# processor_beaglebone.net
KiCad netlist of a schematic drawn in Altium Designer
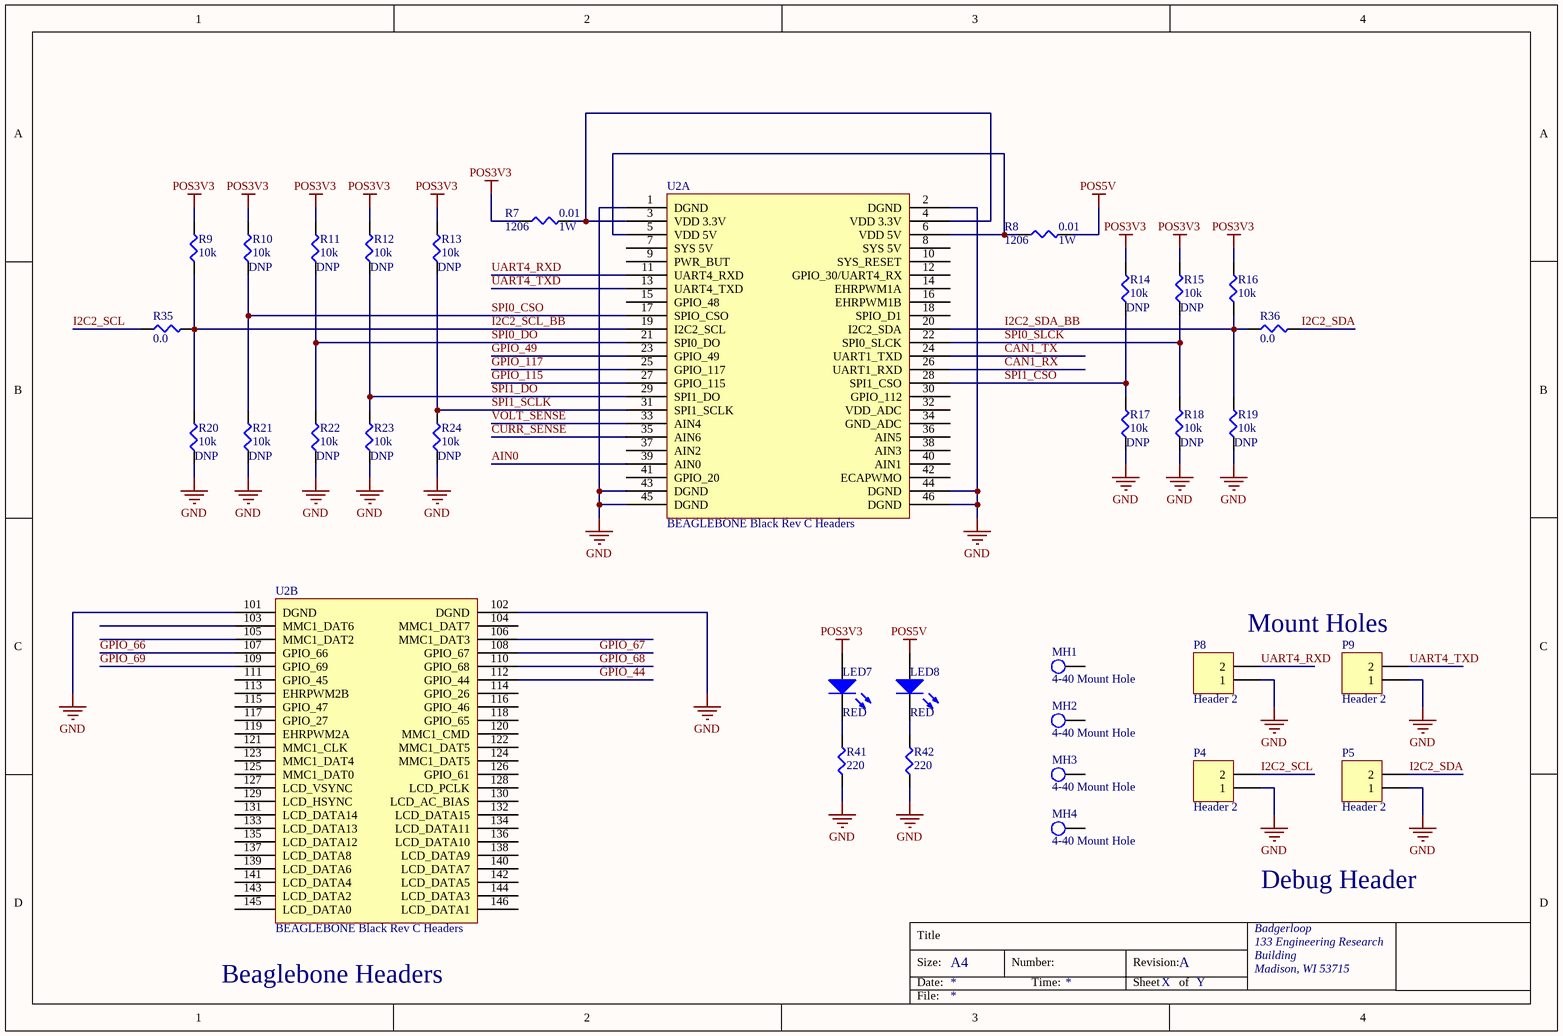
[diagram p0: processor_beaglebone.SchDoc]

(export (version "E")
  (design (tool "Eeschema 10.0.6"))
  (components
    (comp (ref "LED7")
      (value "RED")
      (footprint "LED 0603 RED")
      (description "Red 631nm LED Indication - Discrete 2V 0603 (1608 Metric)")
      (fields (field (name "MANUFACTURER") "Lite-On Inc."))
      (libsource (lib "misc") (part "LED RED 0603"))
    )
    (comp (ref "LED8")
      (value "RED")
      (footprint "LED 0603 RED")
      (description "Red 631nm LED Indication - Discrete 2V 0603 (1608 Metric)")
      (fields (field (name "MANUFACTURER") "Lite-On Inc."))
      (libsource (lib "misc") (part "LED RED 0603"))
    )
    (comp (ref "MH1")
      (value "4-40 Mount Hole")
      (footprint "MH")
      (libsource (lib "misc") (part "4-40 Mount Hole"))
    )
    (comp (ref "MH2")
      (value "4-40 Mount Hole")
      (footprint "MH")
      (libsource (lib "misc") (part "4-40 Mount Hole"))
    )
    (comp (ref "MH3")
      (value "4-40 Mount Hole")
      (footprint "MH")
      (libsource (lib "misc") (part "4-40 Mount Hole"))
    )
    (comp (ref "MH4")
      (value "4-40 Mount Hole")
      (footprint "MH")
      (libsource (lib "misc") (part "4-40 Mount Hole"))
    )
    (comp (ref "P4")
      (value "Header 2")
      (footprint "Pin Header 1x2 TH Pitch 2.54mm")
      (description "Header, 2-Pin")
      (fields (field (name "PUBLISHER") "Altium Limited"))
      (libsource (lib "connector") (part "Header 2"))
    )
    (comp (ref "P5")
      (value "Header 2")
      (footprint "Pin Header 1x2 TH Pitch 2.54mm")
      (description "Header, 2-Pin")
      (fields (field (name "PUBLISHER") "Altium Limited"))
      (libsource (lib "connector") (part "Header 2"))
    )
    (comp (ref "P8")
      (value "Header 2")
      (footprint "Pin Header 1x2 TH Pitch 2.54mm")
      (description "Header, 2-Pin")
      (fields (field (name "PUBLISHER") "Altium Limited"))
      (libsource (lib "connector") (part "Header 2"))
    )
    (comp (ref "P9")
      (value "Header 2")
      (footprint "Pin Header 1x2 TH Pitch 2.54mm")
      (description "Header, 2-Pin")
      (fields (field (name "PUBLISHER") "Altium Limited"))
      (libsource (lib "connector") (part "Header 2"))
    )
    (comp (ref "R7")
      (value "0.01")
      (footprint "SMD-1206-RES")
      (description "RES SMD 0.01 OHM 1% 1W 1206")
      (fields
        (field (name "PART NUMBER") "ERJ-8CWFR010V")
        (field (name "DIGI-KEY PART NUMBER") "P0.01BVCT-ND")
        (field (name "POWER (WATTS)") "1W")
        (field (name "SUPPLIER DEVICE PACKAGE") "1206")
      )
      (libsource (lib "resistor") (part "ERJ-8CWFR010V"))
    )
    (comp (ref "R8")
      (value "0.01")
      (footprint "SMD-1206-RES")
      (description "RES SMD 0.01 OHM 1% 1W 1206")
      (fields
        (field (name "PART NUMBER") "ERJ-8CWFR010V")
        (field (name "DIGI-KEY PART NUMBER") "P0.01BVCT-ND")
        (field (name "POWER (WATTS)") "1W")
        (field (name "SUPPLIER DEVICE PACKAGE") "1206")
      )
      (libsource (lib "resistor") (part "ERJ-8CWFR010V"))
    )
    (comp (ref "R9")
      (value "10k")
      (footprint "SMD-0402-RES")
      (description "RES SMD 10K OHM 5% 1/10W 0402")
      (fields (field (name "PART NUMBER") "ERJ-2GEJ103X") (field (name "DIGI-KEY PART NUMBER") "P10KJCT-ND"))
      (libsource (lib "resistor") (part "ERJ-2GEJ103X"))
    )
    (comp (ref "R10")
      (value "10k")
      (footprint "SMD-0402-RES")
      (description "RES SMD 10K OHM 5% 1/10W 0402")
      (fields
        (field (name "PART NUMBER") "ERJ-2GEJ103X")
        (field (name "DIGI-KEY PART NUMBER") "P10KJCT-ND")
        (field (name "DNP") "DNP")
      )
      (libsource (lib "resistor") (part "ERJ-2GEJ103X"))
    )
    (comp (ref "R11")
      (value "10k")
      (footprint "SMD-0402-RES")
      (description "RES SMD 10K OHM 5% 1/10W 0402")
      (fields
        (field (name "PART NUMBER") "ERJ-2GEJ103X")
        (field (name "DIGI-KEY PART NUMBER") "P10KJCT-ND")
        (field (name "DNP") "DNP")
      )
      (libsource (lib "resistor") (part "ERJ-2GEJ103X"))
    )
    (comp (ref "R12")
      (value "10k")
      (footprint "SMD-0402-RES")
      (description "RES SMD 10K OHM 5% 1/10W 0402")
      (fields
        (field (name "PART NUMBER") "ERJ-2GEJ103X")
        (field (name "DIGI-KEY PART NUMBER") "P10KJCT-ND")
        (field (name "DNP") "DNP")
      )
      (libsource (lib "resistor") (part "ERJ-2GEJ103X"))
    )
    (comp (ref "R13")
      (value "10k")
      (footprint "SMD-0402-RES")
      (description "RES SMD 10K OHM 5% 1/10W 0402")
      (fields
        (field (name "PART NUMBER") "ERJ-2GEJ103X")
        (field (name "DIGI-KEY PART NUMBER") "P10KJCT-ND")
        (field (name "DNP") "DNP")
      )
      (libsource (lib "resistor") (part "ERJ-2GEJ103X"))
    )
    (comp (ref "R14")
      (value "10k")
      (footprint "SMD-0402-RES")
      (description "RES SMD 10K OHM 5% 1/10W 0402")
      (fields
        (field (name "PART NUMBER") "ERJ-2GEJ103X")
        (field (name "DIGI-KEY PART NUMBER") "P10KJCT-ND")
        (field (name "DNP") "DNP")
      )
      (libsource (lib "resistor") (part "ERJ-2GEJ103X"))
    )
    (comp (ref "R15")
      (value "10k")
      (footprint "SMD-0402-RES")
      (description "RES SMD 10K OHM 5% 1/10W 0402")
      (fields
        (field (name "PART NUMBER") "ERJ-2GEJ103X")
        (field (name "DIGI-KEY PART NUMBER") "P10KJCT-ND")
        (field (name "DNP") "DNP")
      )
      (libsource (lib "resistor") (part "ERJ-2GEJ103X"))
    )
    (comp (ref "R16")
      (value "10k")
      (footprint "SMD-0402-RES")
      (description "RES SMD 10K OHM 5% 1/10W 0402")
      (fields (field (name "PART NUMBER") "ERJ-2GEJ103X") (field (name "DIGI-KEY PART NUMBER") "P10KJCT-ND"))
      (libsource (lib "resistor") (part "ERJ-2GEJ103X"))
    )
    (comp (ref "R17")
      (value "10k")
      (footprint "SMD-0402-RES")
      (description "RES SMD 10K OHM 5% 1/10W 0402")
      (fields
        (field (name "PART NUMBER") "ERJ-2GEJ103X")
        (field (name "DIGI-KEY PART NUMBER") "P10KJCT-ND")
        (field (name "DNP") "DNP")
      )
      (libsource (lib "resistor") (part "ERJ-2GEJ103X"))
    )
    (comp (ref "R18")
      (value "10k")
      (footprint "SMD-0402-RES")
      (description "RES SMD 10K OHM 5% 1/10W 0402")
      (fields
        (field (name "PART NUMBER") "ERJ-2GEJ103X")
        (field (name "DIGI-KEY PART NUMBER") "P10KJCT-ND")
        (field (name "DNP") "DNP")
      )
      (libsource (lib "resistor") (part "ERJ-2GEJ103X"))
    )
    (comp (ref "R19")
      (value "10k")
      (footprint "SMD-0402-RES")
      (description "RES SMD 10K OHM 5% 1/10W 0402")
      (fields
        (field (name "PART NUMBER") "ERJ-2GEJ103X")
        (field (name "DIGI-KEY PART NUMBER") "P10KJCT-ND")
        (field (name "DNP") "DNP")
      )
      (libsource (lib "resistor") (part "ERJ-2GEJ103X"))
    )
    (comp (ref "R20")
      (value "10k")
      (footprint "SMD-0402-RES")
      (description "RES SMD 10K OHM 5% 1/10W 0402")
      (fields
        (field (name "PART NUMBER") "ERJ-2GEJ103X")
        (field (name "DIGI-KEY PART NUMBER") "P10KJCT-ND")
        (field (name "DNP") "DNP")
      )
      (libsource (lib "resistor") (part "ERJ-2GEJ103X"))
    )
    (comp (ref "R21")
      (value "10k")
      (footprint "SMD-0402-RES")
      (description "RES SMD 10K OHM 5% 1/10W 0402")
      (fields
        (field (name "PART NUMBER") "ERJ-2GEJ103X")
        (field (name "DIGI-KEY PART NUMBER") "P10KJCT-ND")
        (field (name "DNP") "DNP")
      )
      (libsource (lib "resistor") (part "ERJ-2GEJ103X"))
    )
    (comp (ref "R22")
      (value "10k")
      (footprint "SMD-0402-RES")
      (description "RES SMD 10K OHM 5% 1/10W 0402")
      (fields
        (field (name "PART NUMBER") "ERJ-2GEJ103X")
        (field (name "DIGI-KEY PART NUMBER") "P10KJCT-ND")
        (field (name "DNP") "DNP")
      )
      (libsource (lib "resistor") (part "ERJ-2GEJ103X"))
    )
    (comp (ref "R23")
      (value "10k")
      (footprint "SMD-0402-RES")
      (description "RES SMD 10K OHM 5% 1/10W 0402")
      (fields
        (field (name "PART NUMBER") "ERJ-2GEJ103X")
        (field (name "DIGI-KEY PART NUMBER") "P10KJCT-ND")
        (field (name "DNP") "DNP")
      )
      (libsource (lib "resistor") (part "ERJ-2GEJ103X"))
    )
    (comp (ref "R24")
      (value "10k")
      (footprint "SMD-0402-RES")
      (description "RES SMD 10K OHM 5% 1/10W 0402")
      (fields
        (field (name "PART NUMBER") "ERJ-2GEJ103X")
        (field (name "DIGI-KEY PART NUMBER") "P10KJCT-ND")
        (field (name "DNP") "DNP")
      )
      (libsource (lib "resistor") (part "ERJ-2GEJ103X"))
    )
    (comp (ref "R35")
      (value "0.0")
      (footprint "SMD-0402-RES")
      (description "RES SMD 0.0OHM JUMPER 1/10W 0402")
      (fields (field (name "PART NUMBER") "ERJ-2GE0R00X") (field (name "DIGI-KEY PART NUMBER") "P0.0JCT-ND"))
      (libsource (lib "resistor") (part "ERJ-2GE0R00X"))
    )
    (comp (ref "R36")
      (value "0.0")
      (footprint "SMD-0402-RES")
      (description "RES SMD 0.0OHM JUMPER 1/10W 0402")
      (fields (field (name "PART NUMBER") "ERJ-2GE0R00X") (field (name "DIGI-KEY PART NUMBER") "P0.0JCT-ND"))
      (libsource (lib "resistor") (part "ERJ-2GE0R00X"))
    )
    (comp (ref "R41")
      (value "220")
      (footprint "SMD-0805-RES")
      (description "RES SMD 220 OHM 1% 1/8W 0805")
      (fields (field (name "PART NUMBER") "ERJ-6ENF2200V") (field (name "DIGI-KEY PART NUMBER") "P220CCT-ND"))
      (libsource (lib "resistor") (part "ERJ-6ENF2200V"))
    )
    (comp (ref "R42")
      (value "220")
      (footprint "SMD-0805-RES")
      (description "RES SMD 220 OHM 1% 1/8W 0805")
      (fields (field (name "PART NUMBER") "ERJ-6ENF2200V") (field (name "DIGI-KEY PART NUMBER") "P220CCT-ND"))
      (libsource (lib "resistor") (part "ERJ-6ENF2200V"))
    )
    (comp (ref "U2")
      (value "BEAGLEBONE Black Rev C Headers")
      (footprint "Beaglebone_Topside")
      (description "Beaglebone Black Rev C Header")
      (libsource (lib "temp") (part "Beaglebone"))
    )
  )
  (nets
    (net (code "1") (name "/AIN0") (class "Default")
      (node (ref "U2") (pin "39") (pinfunction "AIN0_39") (pintype "passive"))
    )
    (net (code "2") (name "/CAN1_RX") (class "Default")
      (node (ref "U2") (pin "26") (pinfunction "UART1_RXD_26") (pintype "passive"))
    )
    (net (code "3") (name "/CAN1_TX") (class "Default")
      (node (ref "U2") (pin "24") (pinfunction "UART1_TXD_24") (pintype "passive"))
    )
    (net (code "4") (name "/CURR_SENSE") (class "Default")
      (node (ref "U2") (pin "35") (pinfunction "AIN6_35") (pintype "passive"))
    )
    (net (code "5") (name "/GPIO_44") (class "Default")
      (node (ref "U2") (pin "112") (pinfunction "GPIO_44_112") (pintype "passive"))
    )
    (net (code "6") (name "/GPIO_49") (class "Default")
      (node (ref "U2") (pin "23") (pinfunction "GPIO_49_23") (pintype "passive"))
    )
    (net (code "7") (name "/GPIO_66") (class "Default")
      (node (ref "U2") (pin "107") (pinfunction "GPIO_66_107") (pintype "passive"))
    )
    (net (code "8") (name "/GPIO_67") (class "Default")
      (node (ref "U2") (pin "108") (pinfunction "GPIO_67_108") (pintype "passive"))
    )
    (net (code "9") (name "/GPIO_68") (class "Default")
      (node (ref "U2") (pin "110") (pinfunction "GPIO_68_110") (pintype "passive"))
    )
    (net (code "10") (name "/GPIO_69") (class "Default")
      (node (ref "U2") (pin "109") (pinfunction "GPIO_69_109") (pintype "passive"))
    )
    (net (code "11") (name "/GPIO_115") (class "Default")
      (node (ref "U2") (pin "27") (pinfunction "GPIO_115_27") (pintype "passive"))
    )
    (net (code "12") (name "/GPIO_117") (class "Default")
      (node (ref "U2") (pin "25") (pinfunction "GPIO_117_25") (pintype "passive"))
    )
    (net (code "13") (name "/I2C2_SCL") (class "Default")
      (node (ref "P4") (pin "2") (pinfunction "2_2") (pintype "passive"))
      (node (ref "R35") (pin "1") (pinfunction "1_1") (pintype "passive"))
    )
    (net (code "14") (name "/I2C2_SCL_BB") (class "Default")
      (node (ref "R20") (pin "2") (pinfunction "2_2") (pintype "passive"))
      (node (ref "R35") (pin "2") (pinfunction "2_2") (pintype "passive"))
      (node (ref "R9") (pin "1") (pinfunction "1_1") (pintype "passive"))
      (node (ref "U2") (pin "19") (pinfunction "I2C2_SCL_19") (pintype "passive"))
    )
    (net (code "15") (name "/I2C2_SDA") (class "Default")
      (node (ref "P5") (pin "2") (pinfunction "2_2") (pintype "passive"))
      (node (ref "R36") (pin "2") (pinfunction "2_2") (pintype "passive"))
    )
    (net (code "16") (name "/I2C2_SDA_BB") (class "Default")
      (node (ref "R16") (pin "1") (pinfunction "1_1") (pintype "passive"))
      (node (ref "R19") (pin "2") (pinfunction "2_2") (pintype "passive"))
      (node (ref "R36") (pin "1") (pinfunction "1_1") (pintype "passive"))
      (node (ref "U2") (pin "20") (pinfunction "I2C2_SDA_20") (pintype "passive"))
    )
    (net (code "17") (name "/SPI0_CSO") (class "Default")
      (node (ref "R10") (pin "1") (pinfunction "1_1") (pintype "passive"))
      (node (ref "R21") (pin "2") (pinfunction "2_2") (pintype "passive"))
      (node (ref "U2") (pin "17") (pinfunction "SPIO_CSO_17") (pintype "passive"))
    )
    (net (code "18") (name "/SPI0_DO") (class "Default")
      (node (ref "R11") (pin "1") (pinfunction "1_1") (pintype "passive"))
      (node (ref "R22") (pin "2") (pinfunction "2_2") (pintype "passive"))
      (node (ref "U2") (pin "21") (pinfunction "SPI0_DO_21") (pintype "passive"))
    )
    (net (code "19") (name "/SPI0_SLCK") (class "Default")
      (node (ref "R15") (pin "1") (pinfunction "1_1") (pintype "passive"))
      (node (ref "R18") (pin "2") (pinfunction "2_2") (pintype "passive"))
      (node (ref "U2") (pin "22") (pinfunction "SPI0_SLCK_22") (pintype "passive"))
    )
    (net (code "20") (name "/SPI1_CSO") (class "Default")
      (node (ref "R14") (pin "1") (pinfunction "1_1") (pintype "passive"))
      (node (ref "R17") (pin "2") (pinfunction "2_2") (pintype "passive"))
      (node (ref "U2") (pin "28") (pinfunction "SPI1_CSO_28") (pintype "passive"))
    )
    (net (code "21") (name "/SPI1_DO") (class "Default")
      (node (ref "R12") (pin "1") (pinfunction "1_1") (pintype "passive"))
      (node (ref "R23") (pin "2") (pinfunction "2_2") (pintype "passive"))
      (node (ref "U2") (pin "29") (pinfunction "SPI1_DO_29") (pintype "passive"))
    )
    (net (code "22") (name "/SPI1_SCLK") (class "Default")
      (node (ref "R13") (pin "1") (pinfunction "1_1") (pintype "passive"))
      (node (ref "R24") (pin "2") (pinfunction "2_2") (pintype "passive"))
      (node (ref "U2") (pin "31") (pinfunction "SPI1_SCLK_31") (pintype "passive"))
    )
    (net (code "23") (name "/UART4_RXD") (class "Default")
      (node (ref "P8") (pin "2") (pinfunction "2_2") (pintype "passive"))
      (node (ref "U2") (pin "11") (pinfunction "UART4_RXD_11") (pintype "passive"))
    )
    (net (code "24") (name "/UART4_TXD") (class "Default")
      (node (ref "P9") (pin "2") (pinfunction "2_2") (pintype "passive"))
      (node (ref "U2") (pin "13") (pinfunction "UART4_TXD_13") (pintype "passive"))
    )
    (net (code "25") (name "/VOLT_SENSE") (class "Default")
      (node (ref "U2") (pin "33") (pinfunction "AIN4_33") (pintype "passive"))
    )
    (net (code "26") (name "GND") (class "Default")
      (node (ref "P4") (pin "1") (pinfunction "1_1") (pintype "passive"))
      (node (ref "P5") (pin "1") (pinfunction "1_1") (pintype "passive"))
      (node (ref "P8") (pin "1") (pinfunction "1_1") (pintype "passive"))
      (node (ref "P9") (pin "1") (pinfunction "1_1") (pintype "passive"))
      (node (ref "R17") (pin "1") (pinfunction "1_1") (pintype "passive"))
      (node (ref "R18") (pin "1") (pinfunction "1_1") (pintype "passive"))
      (node (ref "R19") (pin "1") (pinfunction "1_1") (pintype "passive"))
      (node (ref "R20") (pin "1") (pinfunction "1_1") (pintype "passive"))
      (node (ref "R21") (pin "1") (pinfunction "1_1") (pintype "passive"))
      (node (ref "R22") (pin "1") (pinfunction "1_1") (pintype "passive"))
      (node (ref "R23") (pin "1") (pinfunction "1_1") (pintype "passive"))
      (node (ref "R24") (pin "1") (pinfunction "1_1") (pintype "passive"))
      (node (ref "R41") (pin "1") (pinfunction "1_1") (pintype "passive"))
      (node (ref "R42") (pin "1") (pinfunction "1_1") (pintype "passive"))
      (node (ref "U2") (pin "1") (pinfunction "DGND_1") (pintype "passive"))
      (node (ref "U2") (pin "101") (pinfunction "DGND_101") (pintype "passive"))
      (node (ref "U2") (pin "102") (pinfunction "DGND_102") (pintype "passive"))
      (node (ref "U2") (pin "2") (pinfunction "DGND_2") (pintype "passive"))
      (node (ref "U2") (pin "43") (pinfunction "DGND_43") (pintype "passive"))
      (node (ref "U2") (pin "44") (pinfunction "DGND_44") (pintype "passive"))
      (node (ref "U2") (pin "45") (pinfunction "DGND_45") (pintype "passive"))
      (node (ref "U2") (pin "46") (pinfunction "DGND_46") (pintype "passive"))
    )
    (net (code "27") (name "Net-(LED7-K)") (class "Default")
      (node (ref "LED7") (pin "2") (pinfunction "K_2") (pintype "passive"))
      (node (ref "R41") (pin "2") (pinfunction "2_2") (pintype "passive"))
    )
    (net (code "28") (name "Net-(LED8-K)") (class "Default")
      (node (ref "LED8") (pin "2") (pinfunction "K_2") (pintype "passive"))
      (node (ref "R42") (pin "2") (pinfunction "2_2") (pintype "passive"))
    )
    (net (code "29") (name "Net-(R7-Pad2)") (class "Default")
      (node (ref "R7") (pin "2") (pinfunction "2_2") (pintype "passive"))
      (node (ref "U2") (pin "3") (pinfunction "VDD_3.3V_3") (pintype "passive"))
      (node (ref "U2") (pin "4") (pinfunction "VDD_3.3V_4") (pintype "passive"))
    )
    (net (code "30") (name "Net-(R8-Pad1)") (class "Default")
      (node (ref "R8") (pin "1") (pinfunction "1_1") (pintype "passive"))
      (node (ref "U2") (pin "5") (pinfunction "VDD_5V_5") (pintype "passive"))
      (node (ref "U2") (pin "6") (pinfunction "VDD_5V_6") (pintype "passive"))
    )
    (net (code "31") (name "POS3V3") (class "Default")
      (node (ref "LED7") (pin "1") (pinfunction "A_1") (pintype "passive"))
      (node (ref "R10") (pin "2") (pinfunction "2_2") (pintype "passive"))
      (node (ref "R11") (pin "2") (pinfunction "2_2") (pintype "passive"))
      (node (ref "R12") (pin "2") (pinfunction "2_2") (pintype "passive"))
      (node (ref "R13") (pin "2") (pinfunction "2_2") (pintype "passive"))
      (node (ref "R14") (pin "2") (pinfunction "2_2") (pintype "passive"))
      (node (ref "R15") (pin "2") (pinfunction "2_2") (pintype "passive"))
      (node (ref "R16") (pin "2") (pinfunction "2_2") (pintype "passive"))
      (node (ref "R7") (pin "1") (pinfunction "1_1") (pintype "passive"))
      (node (ref "R9") (pin "2") (pinfunction "2_2") (pintype "passive"))
    )
    (net (code "32") (name "POS5V") (class "Default")
      (node (ref "LED8") (pin "1") (pinfunction "A_1") (pintype "passive"))
      (node (ref "R8") (pin "2") (pinfunction "2_2") (pintype "passive"))
    )
    (net (code "33") (name "unconnected-(MH1-Pad46)") (class "Default")
      (node (ref "MH1") (pin "46") (pinfunction "46_46") (pintype "passive"))
    )
    (net (code "34") (name "unconnected-(MH2-Pad46)") (class "Default")
      (node (ref "MH2") (pin "46") (pinfunction "46_46") (pintype "passive"))
    )
    (net (code "35") (name "unconnected-(MH3-Pad46)") (class "Default")
      (node (ref "MH3") (pin "46") (pinfunction "46_46") (pintype "passive"))
    )
    (net (code "36") (name "unconnected-(MH4-Pad46)") (class "Default")
      (node (ref "MH4") (pin "46") (pinfunction "46_46") (pintype "passive"))
    )
    (net (code "37") (name "unconnected-(U2A-AIN1-Pad40)") (class "Default")
      (node (ref "U2") (pin "40") (pinfunction "AIN1_40") (pintype "passive"))
    )
    (net (code "38") (name "unconnected-(U2A-AIN2-Pad37)") (class "Default")
      (node (ref "U2") (pin "37") (pinfunction "AIN2_37") (pintype "passive"))
    )
    (net (code "39") (name "unconnected-(U2A-AIN3-Pad38)") (class "Default")
      (node (ref "U2") (pin "38") (pinfunction "AIN3_38") (pintype "passive"))
    )
    (net (code "40") (name "unconnected-(U2A-AIN5-Pad36)") (class "Default")
      (node (ref "U2") (pin "36") (pinfunction "AIN5_36") (pintype "passive"))
    )
    (net (code "41") (name "unconnected-(U2A-ECAPWMO-Pad42)") (class "Default")
      (node (ref "U2") (pin "42") (pinfunction "ECAPWMO_42") (pintype "passive"))
    )
    (net (code "42") (name "unconnected-(U2A-EHRPWM1A-Pad14)") (class "Default")
      (node (ref "U2") (pin "14") (pinfunction "EHRPWM1A_14") (pintype "passive"))
    )
    (net (code "43") (name "unconnected-(U2A-EHRPWM1B-Pad16)") (class "Default")
      (node (ref "U2") (pin "16") (pinfunction "EHRPWM1B_16") (pintype "passive"))
    )
    (net (code "44") (name "unconnected-(U2A-GND_ADC-Pad34)") (class "Default")
      (node (ref "U2") (pin "34") (pinfunction "GND_ADC_34") (pintype "passive"))
    )
    (net (code "45") (name "unconnected-(U2A-GPIO_20-Pad41)") (class "Default")
      (node (ref "U2") (pin "41") (pinfunction "GPIO_20_41") (pintype "passive"))
    )
    (net (code "46") (name "unconnected-(U2A-GPIO_30{slash}UART4_RX-Pad12)") (class "Default")
      (node (ref "U2") (pin "12") (pinfunction "GPIO_30/UART4_RX_12") (pintype "passive"))
    )
    (net (code "47") (name "unconnected-(U2A-GPIO_48-Pad15)") (class "Default")
      (node (ref "U2") (pin "15") (pinfunction "GPIO_48_15") (pintype "passive"))
    )
    (net (code "48") (name "unconnected-(U2A-GPIO_112-Pad30)") (class "Default")
      (node (ref "U2") (pin "30") (pinfunction "GPIO_112_30") (pintype "passive"))
    )
    (net (code "49") (name "unconnected-(U2A-PWR_BUT-Pad9)") (class "Default")
      (node (ref "U2") (pin "9") (pinfunction "PWR_BUT_9") (pintype "passive"))
    )
    (net (code "50") (name "unconnected-(U2A-SPIO_D1-Pad18)") (class "Default")
      (node (ref "U2") (pin "18") (pinfunction "SPIO_D1_18") (pintype "passive"))
    )
    (net (code "51") (name "unconnected-(U2A-SYS_5V-Pad7)") (class "Default")
      (node (ref "U2") (pin "7") (pinfunction "SYS_5V_7") (pintype "passive"))
    )
    (net (code "52") (name "unconnected-(U2A-SYS_5V-Pad8)") (class "Default")
      (node (ref "U2") (pin "8") (pinfunction "SYS_5V_8") (pintype "passive"))
    )
    (net (code "53") (name "unconnected-(U2A-SYS_RESET-Pad10)") (class "Default")
      (node (ref "U2") (pin "10") (pinfunction "SYS_RESET_10") (pintype "passive"))
    )
    (net (code "54") (name "unconnected-(U2A-VDD_ADC-Pad32)") (class "Default")
      (node (ref "U2") (pin "32") (pinfunction "VDD_ADC_32") (pintype "passive"))
    )
    (net (code "55") (name "unconnected-(U2B-EHRPWM2A-Pad119)") (class "Default")
      (node (ref "U2") (pin "119") (pinfunction "EHRPWM2A_119") (pintype "passive"))
    )
    (net (code "56") (name "unconnected-(U2B-EHRPWM2B-Pad113)") (class "Default")
      (node (ref "U2") (pin "113") (pinfunction "EHRPWM2B_113") (pintype "passive"))
    )
    (net (code "57") (name "unconnected-(U2B-GPIO_26-Pad114)") (class "Default")
      (node (ref "U2") (pin "114") (pinfunction "GPIO_26_114") (pintype "passive"))
    )
    (net (code "58") (name "unconnected-(U2B-GPIO_27-Pad117)") (class "Default")
      (node (ref "U2") (pin "117") (pinfunction "GPIO_27_117") (pintype "passive"))
    )
    (net (code "59") (name "unconnected-(U2B-GPIO_45-Pad111)") (class "Default")
      (node (ref "U2") (pin "111") (pinfunction "GPIO_45_111") (pintype "passive"))
    )
    (net (code "60") (name "unconnected-(U2B-GPIO_46-Pad116)") (class "Default")
      (node (ref "U2") (pin "116") (pinfunction "GPIO_46_116") (pintype "passive"))
    )
    (net (code "61") (name "unconnected-(U2B-GPIO_47-Pad115)") (class "Default")
      (node (ref "U2") (pin "115") (pinfunction "GPIO_47_115") (pintype "passive"))
    )
    (net (code "62") (name "unconnected-(U2B-GPIO_61-Pad126)") (class "Default")
      (node (ref "U2") (pin "126") (pinfunction "GPIO_61_126") (pintype "passive"))
    )
    (net (code "63") (name "unconnected-(U2B-GPIO_65-Pad118)") (class "Default")
      (node (ref "U2") (pin "118") (pinfunction "GPIO_65_118") (pintype "passive"))
    )
    (net (code "64") (name "unconnected-(U2B-LCD_AC_BIAS-Pad130)") (class "Default")
      (node (ref "U2") (pin "130") (pinfunction "LCD_AC_BIAS_130") (pintype "passive"))
    )
    (net (code "65") (name "unconnected-(U2B-LCD_DATA0-Pad145)") (class "Default")
      (node (ref "U2") (pin "145") (pinfunction "LCD_DATA0_145") (pintype "passive"))
    )
    (net (code "66") (name "unconnected-(U2B-LCD_DATA1-Pad146)") (class "Default")
      (node (ref "U2") (pin "146") (pinfunction "LCD_DATA1_146") (pintype "passive"))
    )
    (net (code "67") (name "unconnected-(U2B-LCD_DATA2-Pad143)") (class "Default")
      (node (ref "U2") (pin "143") (pinfunction "LCD_DATA2_143") (pintype "passive"))
    )
    (net (code "68") (name "unconnected-(U2B-LCD_DATA3-Pad144)") (class "Default")
      (node (ref "U2") (pin "144") (pinfunction "LCD_DATA3_144") (pintype "passive"))
    )
    (net (code "69") (name "unconnected-(U2B-LCD_DATA4-Pad141)") (class "Default")
      (node (ref "U2") (pin "141") (pinfunction "LCD_DATA4_141") (pintype "passive"))
    )
    (net (code "70") (name "unconnected-(U2B-LCD_DATA5-Pad142)") (class "Default")
      (node (ref "U2") (pin "142") (pinfunction "LCD_DATA5_142") (pintype "passive"))
    )
    (net (code "71") (name "unconnected-(U2B-LCD_DATA6-Pad139)") (class "Default")
      (node (ref "U2") (pin "139") (pinfunction "LCD_DATA6_139") (pintype "passive"))
    )
    (net (code "72") (name "unconnected-(U2B-LCD_DATA7-Pad140)") (class "Default")
      (node (ref "U2") (pin "140") (pinfunction "LCD_DATA7_140") (pintype "passive"))
    )
    (net (code "73") (name "unconnected-(U2B-LCD_DATA8-Pad137)") (class "Default")
      (node (ref "U2") (pin "137") (pinfunction "LCD_DATA8_137") (pintype "passive"))
    )
    (net (code "74") (name "unconnected-(U2B-LCD_DATA9-Pad138)") (class "Default")
      (node (ref "U2") (pin "138") (pinfunction "LCD_DATA9_138") (pintype "passive"))
    )
    (net (code "75") (name "unconnected-(U2B-LCD_DATA10-Pad136)") (class "Default")
      (node (ref "U2") (pin "136") (pinfunction "LCD_DATA10_136") (pintype "passive"))
    )
    (net (code "76") (name "unconnected-(U2B-LCD_DATA11-Pad134)") (class "Default")
      (node (ref "U2") (pin "134") (pinfunction "LCD_DATA11_134") (pintype "passive"))
    )
    (net (code "77") (name "unconnected-(U2B-LCD_DATA12-Pad135)") (class "Default")
      (node (ref "U2") (pin "135") (pinfunction "LCD_DATA12_135") (pintype "passive"))
    )
    (net (code "78") (name "unconnected-(U2B-LCD_DATA13-Pad133)") (class "Default")
      (node (ref "U2") (pin "133") (pinfunction "LCD_DATA13_133") (pintype "passive"))
    )
    (net (code "79") (name "unconnected-(U2B-LCD_DATA14-Pad131)") (class "Default")
      (node (ref "U2") (pin "131") (pinfunction "LCD_DATA14_131") (pintype "passive"))
    )
    (net (code "80") (name "unconnected-(U2B-LCD_DATA15-Pad132)") (class "Default")
      (node (ref "U2") (pin "132") (pinfunction "LCD_DATA15_132") (pintype "passive"))
    )
    (net (code "81") (name "unconnected-(U2B-LCD_HSYNC-Pad129)") (class "Default")
      (node (ref "U2") (pin "129") (pinfunction "LCD_HSYNC_129") (pintype "passive"))
    )
    (net (code "82") (name "unconnected-(U2B-LCD_PCLK-Pad128)") (class "Default")
      (node (ref "U2") (pin "128") (pinfunction "LCD_PCLK_128") (pintype "passive"))
    )
    (net (code "83") (name "unconnected-(U2B-LCD_VSYNC-Pad127)") (class "Default")
      (node (ref "U2") (pin "127") (pinfunction "LCD_VSYNC_127") (pintype "passive"))
    )
    (net (code "84") (name "unconnected-(U2B-MMC1_CLK-Pad121)") (class "Default")
      (node (ref "U2") (pin "121") (pinfunction "MMC1_CLK_121") (pintype "passive"))
    )
    (net (code "85") (name "unconnected-(U2B-MMC1_CMD-Pad120)") (class "Default")
      (node (ref "U2") (pin "120") (pinfunction "MMC1_CMD_120") (pintype "passive"))
    )
    (net (code "86") (name "unconnected-(U2B-MMC1_DAT0-Pad125)") (class "Default")
      (node (ref "U2") (pin "125") (pinfunction "MMC1_DAT0_125") (pintype "passive"))
    )
    (net (code "87") (name "unconnected-(U2B-MMC1_DAT2-Pad105)") (class "Default")
      (node (ref "U2") (pin "105") (pinfunction "MMC1_DAT2_105") (pintype "passive"))
    )
    (net (code "88") (name "unconnected-(U2B-MMC1_DAT3-Pad106)") (class "Default")
      (node (ref "U2") (pin "106") (pinfunction "MMC1_DAT3_106") (pintype "passive"))
    )
    (net (code "89") (name "unconnected-(U2B-MMC1_DAT4-Pad123)") (class "Default")
      (node (ref "U2") (pin "123") (pinfunction "MMC1_DAT4_123") (pintype "passive"))
    )
    (net (code "90") (name "unconnected-(U2B-MMC1_DAT5-Pad122)") (class "Default")
      (node (ref "U2") (pin "122") (pinfunction "MMC1_DAT5_122") (pintype "passive"))
    )
    (net (code "91") (name "unconnected-(U2B-MMC1_DAT5-Pad124)") (class "Default")
      (node (ref "U2") (pin "124") (pinfunction "MMC1_DAT5_124") (pintype "passive"))
    )
    (net (code "92") (name "unconnected-(U2B-MMC1_DAT6-Pad103)") (class "Default")
      (node (ref "U2") (pin "103") (pinfunction "MMC1_DAT6_103") (pintype "passive"))
    )
    (net (code "93") (name "unconnected-(U2B-MMC1_DAT7-Pad104)") (class "Default")
      (node (ref "U2") (pin "104") (pinfunction "MMC1_DAT7_104") (pintype "passive"))
    )
  )
)
